# Commodore_KB_Tester.net
KiCad netlist of a schematic drawn in EAGLE
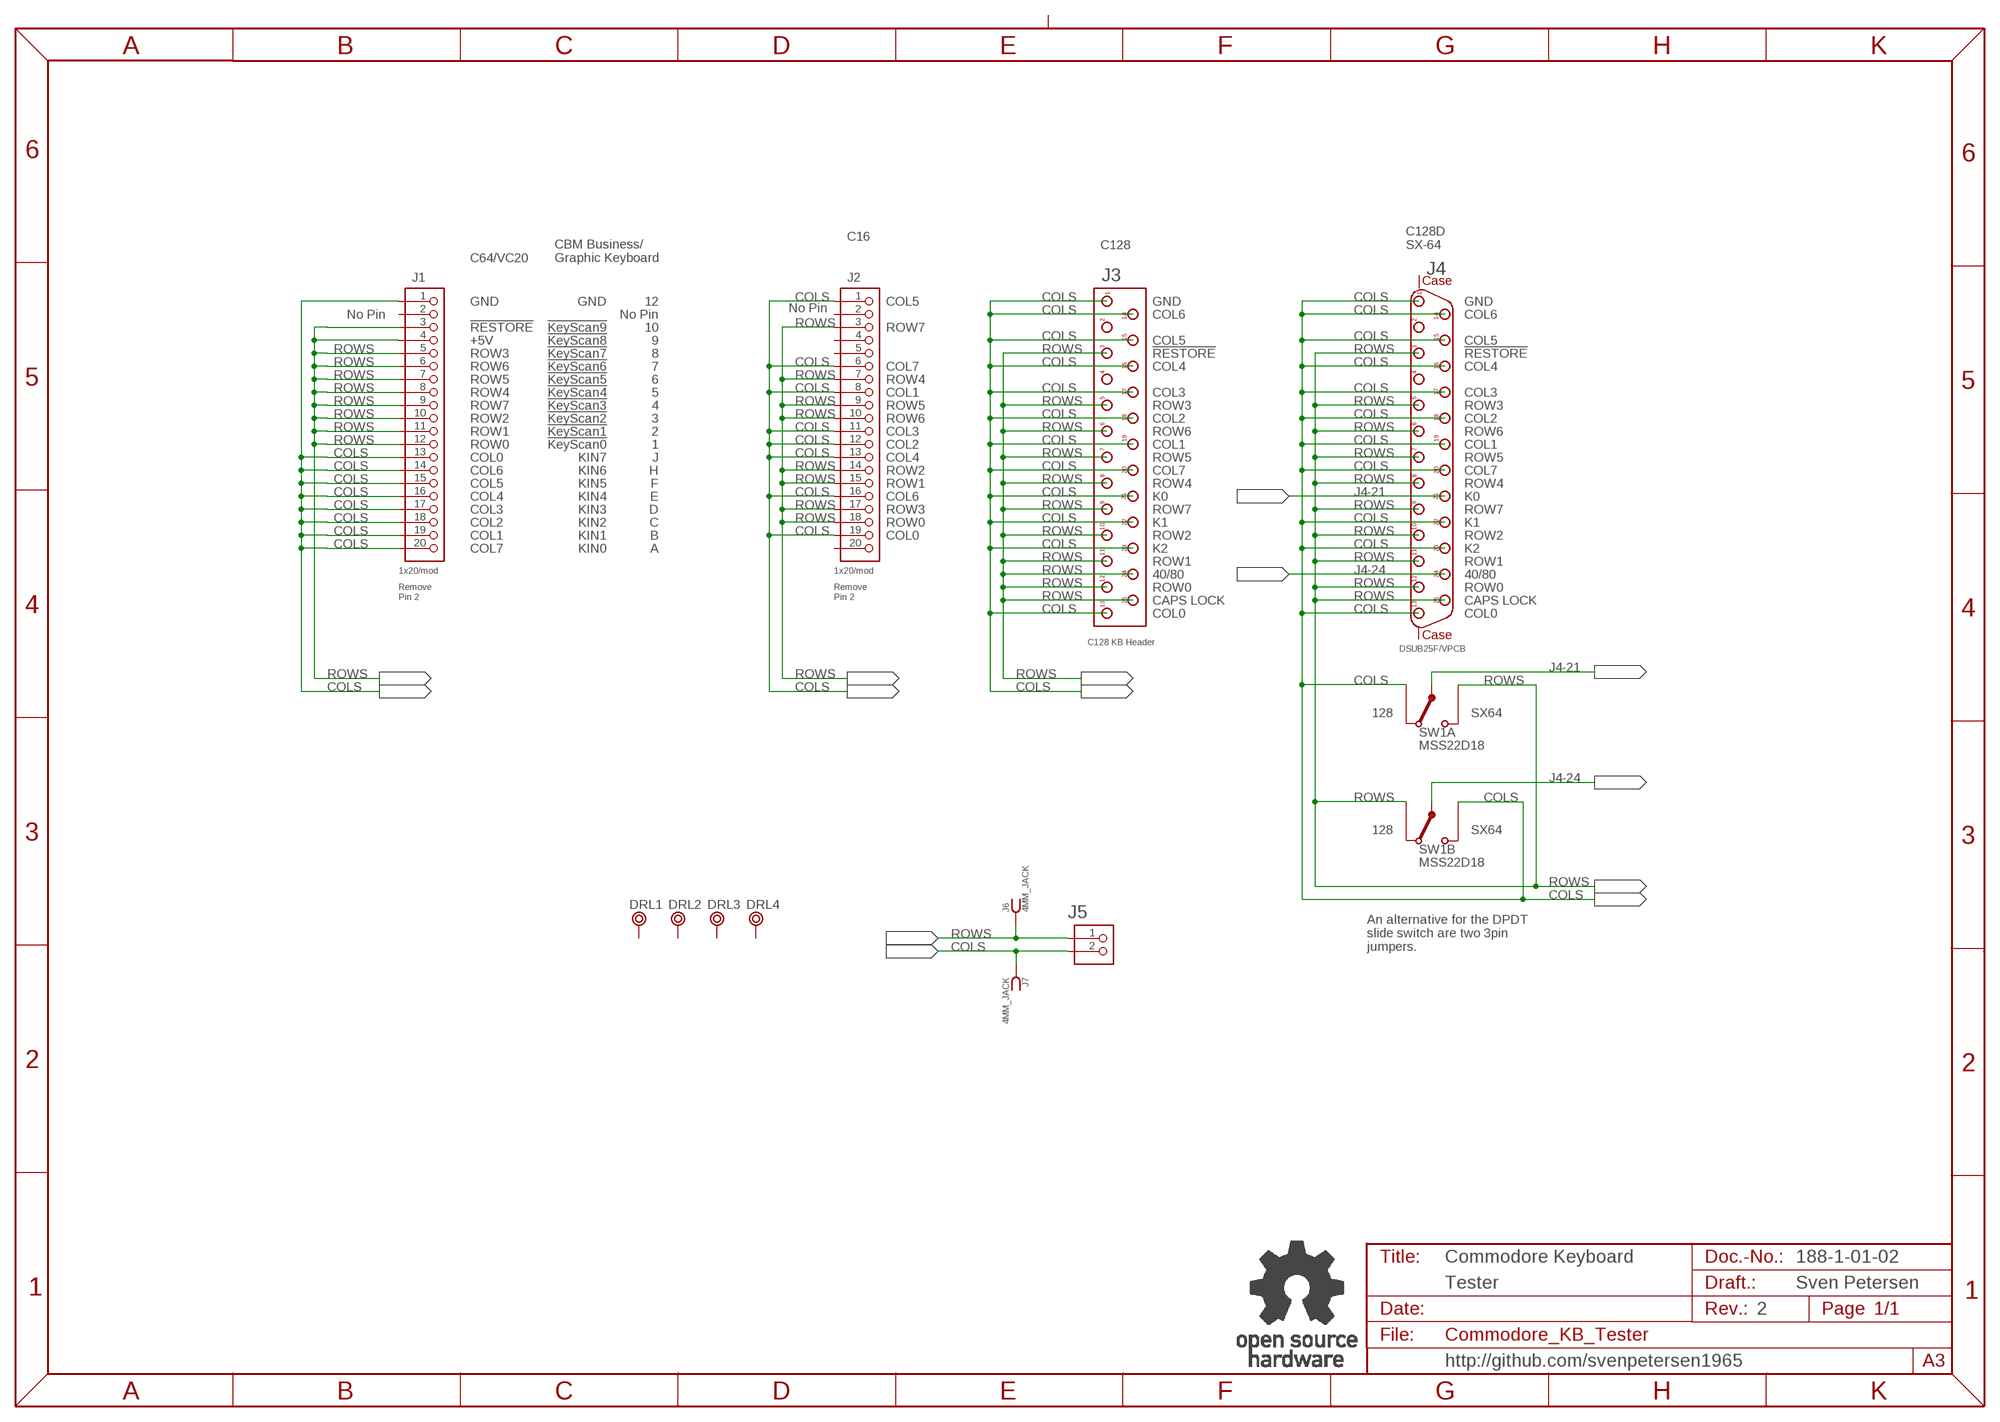
[diagram p0: schematic, sheet 1]

(export (version "E")
  (design (tool "Eeschema 10.0.6"))
  (components
    (comp (ref "DRL1")
      (value "BOHR3,5")
      (footprint "eagle-import:BOHR3,5")
      (libsource (lib "eagle-import") (part "BOHR3,5"))
    )
    (comp (ref "DRL2")
      (value "BOHR3,5")
      (footprint "eagle-import:BOHR3,5")
      (libsource (lib "eagle-import") (part "BOHR3,5"))
    )
    (comp (ref "DRL3")
      (value "BOHR3,5")
      (footprint "eagle-import:BOHR3,5")
      (libsource (lib "eagle-import") (part "BOHR3,5"))
    )
    (comp (ref "DRL4")
      (value "BOHR3,5")
      (footprint "eagle-import:BOHR3,5")
      (libsource (lib "eagle-import") (part "BOHR3,5"))
    )
    (comp (ref "J1")
      (value "1x20/mod")
      (footprint "eagle-import:1X20")
      (libsource (lib "eagle-import") (part "PINHD-1X20"))
    )
    (comp (ref "J2")
      (value "1x20/mod")
      (footprint "eagle-import:1X20")
      (libsource (lib "eagle-import") (part "PINHD-1X20"))
    )
    (comp (ref "J3")
      (value "C128 KB Header")
      (footprint "eagle-import:C128KB_HEADER")
      (libsource (lib "eagle-import") (part "C128_KBHEADER"))
    )
    (comp (ref "J4")
      (value "DSUB25F/VPCB")
      (footprint "eagle-import:DS25F-V")
      (libsource (lib "eagle-import") (part "DS25F-V-CL"))
    )
    (comp (ref "J5")
      (value "PINHD-1X2")
      (footprint "eagle-import:1X02")
      (libsource (lib "eagle-import") (part "PINHD-1X2"))
    )
    (comp (ref "J6")
      (value "4MM_JACK")
      (footprint "eagle-import:JACK4MM")
      (libsource (lib "eagle-import") (part "4MM_JACK"))
    )
    (comp (ref "J7")
      (value "4MM_JACK")
      (footprint "eagle-import:JACK4MM")
      (libsource (lib "eagle-import") (part "4MM_JACK"))
    )
    (comp (ref "SW1")
      (value "MSS22D18")
      (footprint "eagle-import:DPDT_9MM")
      (libsource (lib "eagle-import") (part "DPDT_9MM"))
    )
    (comp (ref "U$12")
      (value "OPEN_SOURCE_HW")
      (footprint "eagle-import:OPENHW")
      (libsource (lib "eagle-import") (part "OPEN_SOURCE_HW"))
    )
  )
  (nets
    (net (code "1") (name "/COLS") (class "Default")
      (node (ref "J1") (pin "1") (pinfunction "1_1") (pintype "passive"))
      (node (ref "J1") (pin "13") (pinfunction "13_13") (pintype "passive"))
      (node (ref "J1") (pin "14") (pinfunction "14_14") (pintype "passive"))
      (node (ref "J1") (pin "15") (pinfunction "15_15") (pintype "passive"))
      (node (ref "J1") (pin "16") (pinfunction "16_16") (pintype "passive"))
      (node (ref "J1") (pin "17") (pinfunction "17_17") (pintype "passive"))
      (node (ref "J1") (pin "18") (pinfunction "18_18") (pintype "passive"))
      (node (ref "J1") (pin "19") (pinfunction "19_19") (pintype "passive"))
      (node (ref "J1") (pin "20") (pinfunction "20_20") (pintype "passive"))
      (node (ref "J2") (pin "1") (pinfunction "1_1") (pintype "passive"))
      (node (ref "J2") (pin "11") (pinfunction "11_11") (pintype "passive"))
      (node (ref "J2") (pin "12") (pinfunction "12_12") (pintype "passive"))
      (node (ref "J2") (pin "13") (pinfunction "13_13") (pintype "passive"))
      (node (ref "J2") (pin "16") (pinfunction "16_16") (pintype "passive"))
      (node (ref "J2") (pin "19") (pinfunction "19_19") (pintype "passive"))
      (node (ref "J2") (pin "6") (pinfunction "6_6") (pintype "passive"))
      (node (ref "J2") (pin "8") (pinfunction "8_8") (pintype "passive"))
      (node (ref "J3") (pin "1") (pinfunction "1_1") (pintype "passive"))
      (node (ref "J3") (pin "13") (pinfunction "13_13") (pintype "passive"))
      (node (ref "J3") (pin "14") (pinfunction "14_14") (pintype "passive"))
      (node (ref "J3") (pin "15") (pinfunction "15_15") (pintype "passive"))
      (node (ref "J3") (pin "16") (pinfunction "16_16") (pintype "passive"))
      (node (ref "J3") (pin "17") (pinfunction "17_17") (pintype "passive"))
      (node (ref "J3") (pin "18") (pinfunction "18_18") (pintype "passive"))
      (node (ref "J3") (pin "19") (pinfunction "19_19") (pintype "passive"))
      (node (ref "J3") (pin "20") (pinfunction "20_20") (pintype "passive"))
      (node (ref "J3") (pin "21") (pinfunction "21_21") (pintype "passive"))
      (node (ref "J3") (pin "22") (pinfunction "22_22") (pintype "passive"))
      (node (ref "J3") (pin "23") (pinfunction "23_23") (pintype "passive"))
      (node (ref "J4") (pin "1") (pinfunction "1_1") (pintype "passive"))
      (node (ref "J4") (pin "13") (pinfunction "13_13") (pintype "passive"))
      (node (ref "J4") (pin "14") (pinfunction "14_14") (pintype "passive"))
      (node (ref "J4") (pin "15") (pinfunction "15_15") (pintype "passive"))
      (node (ref "J4") (pin "16") (pinfunction "16_16") (pintype "passive"))
      (node (ref "J4") (pin "17") (pinfunction "17_17") (pintype "passive"))
      (node (ref "J4") (pin "18") (pinfunction "18_18") (pintype "passive"))
      (node (ref "J4") (pin "19") (pinfunction "19_19") (pintype "passive"))
      (node (ref "J4") (pin "20") (pinfunction "20_20") (pintype "passive"))
      (node (ref "J4") (pin "22") (pinfunction "22_22") (pintype "passive"))
      (node (ref "J4") (pin "23") (pinfunction "23_23") (pintype "passive"))
      (node (ref "J5") (pin "2") (pinfunction "2_2") (pintype "passive"))
      (node (ref "J7") (pin "1") (pinfunction "1_1") (pintype "bidirectional"))
      (node (ref "J7") (pin "1A") (pinfunction "1_1A") (pintype "bidirectional"))
      (node (ref "SW1") (pin "3") (pinfunction "DWN_3") (pintype "bidirectional"))
      (node (ref "SW1") (pin "6") (pinfunction "UP_6") (pintype "bidirectional"))
    )
    (net (code "2") (name "/J4-21") (class "Default")
      (node (ref "J4") (pin "21") (pinfunction "21_21") (pintype "passive"))
      (node (ref "SW1") (pin "2") (pinfunction "COM_2") (pintype "bidirectional"))
    )
    (net (code "3") (name "/J4-24") (class "Default")
      (node (ref "J4") (pin "24") (pinfunction "24_24") (pintype "passive"))
      (node (ref "SW1") (pin "5") (pinfunction "COM_5") (pintype "bidirectional"))
    )
    (net (code "4") (name "/ROWS") (class "Default")
      (node (ref "J1") (pin "10") (pinfunction "10_10") (pintype "passive"))
      (node (ref "J1") (pin "11") (pinfunction "11_11") (pintype "passive"))
      (node (ref "J1") (pin "12") (pinfunction "12_12") (pintype "passive"))
      (node (ref "J1") (pin "3") (pinfunction "3_3") (pintype "passive"))
      (node (ref "J1") (pin "4") (pinfunction "4_4") (pintype "passive"))
      (node (ref "J1") (pin "5") (pinfunction "5_5") (pintype "passive"))
      (node (ref "J1") (pin "6") (pinfunction "6_6") (pintype "passive"))
      (node (ref "J1") (pin "7") (pinfunction "7_7") (pintype "passive"))
      (node (ref "J1") (pin "8") (pinfunction "8_8") (pintype "passive"))
      (node (ref "J1") (pin "9") (pinfunction "9_9") (pintype "passive"))
      (node (ref "J2") (pin "10") (pinfunction "10_10") (pintype "passive"))
      (node (ref "J2") (pin "14") (pinfunction "14_14") (pintype "passive"))
      (node (ref "J2") (pin "15") (pinfunction "15_15") (pintype "passive"))
      (node (ref "J2") (pin "17") (pinfunction "17_17") (pintype "passive"))
      (node (ref "J2") (pin "18") (pinfunction "18_18") (pintype "passive"))
      (node (ref "J2") (pin "3") (pinfunction "3_3") (pintype "passive"))
      (node (ref "J2") (pin "7") (pinfunction "7_7") (pintype "passive"))
      (node (ref "J2") (pin "9") (pinfunction "9_9") (pintype "passive"))
      (node (ref "J3") (pin "10") (pinfunction "10_10") (pintype "passive"))
      (node (ref "J3") (pin "11") (pinfunction "11_11") (pintype "passive"))
      (node (ref "J3") (pin "12") (pinfunction "12_12") (pintype "passive"))
      (node (ref "J3") (pin "24") (pinfunction "24_24") (pintype "passive"))
      (node (ref "J3") (pin "25") (pinfunction "25_25") (pintype "passive"))
      (node (ref "J3") (pin "3") (pinfunction "3_3") (pintype "passive"))
      (node (ref "J3") (pin "5") (pinfunction "5_5") (pintype "passive"))
      (node (ref "J3") (pin "6") (pinfunction "6_6") (pintype "passive"))
      (node (ref "J3") (pin "7") (pinfunction "7_7") (pintype "passive"))
      (node (ref "J3") (pin "8") (pinfunction "8_8") (pintype "passive"))
      (node (ref "J3") (pin "9") (pinfunction "9_9") (pintype "passive"))
      (node (ref "J4") (pin "10") (pinfunction "10_10") (pintype "passive"))
      (node (ref "J4") (pin "11") (pinfunction "11_11") (pintype "passive"))
      (node (ref "J4") (pin "12") (pinfunction "12_12") (pintype "passive"))
      (node (ref "J4") (pin "25") (pinfunction "25_25") (pintype "passive"))
      (node (ref "J4") (pin "3") (pinfunction "3_3") (pintype "passive"))
      (node (ref "J4") (pin "5") (pinfunction "5_5") (pintype "passive"))
      (node (ref "J4") (pin "6") (pinfunction "6_6") (pintype "passive"))
      (node (ref "J4") (pin "7") (pinfunction "7_7") (pintype "passive"))
      (node (ref "J4") (pin "8") (pinfunction "8_8") (pintype "passive"))
      (node (ref "J4") (pin "9") (pinfunction "9_9") (pintype "passive"))
      (node (ref "J5") (pin "1") (pinfunction "1_1") (pintype "passive"))
      (node (ref "J6") (pin "1") (pinfunction "1_1") (pintype "bidirectional"))
      (node (ref "J6") (pin "1A") (pinfunction "1_1A") (pintype "bidirectional"))
      (node (ref "SW1") (pin "1") (pinfunction "UP_1") (pintype "bidirectional"))
      (node (ref "SW1") (pin "4") (pinfunction "DWN_4") (pintype "bidirectional"))
    )
    (net (code "5") (name "unconnected-(DRL1-PadP$1)") (class "Default")
      (node (ref "DRL1") (pin "P$1") (pinfunction "P$1_P$1") (pintype "passive"))
    )
    (net (code "6") (name "unconnected-(DRL2-PadP$1)") (class "Default")
      (node (ref "DRL2") (pin "P$1") (pinfunction "P$1_P$1") (pintype "passive"))
    )
    (net (code "7") (name "unconnected-(DRL3-PadP$1)") (class "Default")
      (node (ref "DRL3") (pin "P$1") (pinfunction "P$1_P$1") (pintype "passive"))
    )
    (net (code "8") (name "unconnected-(DRL4-PadP$1)") (class "Default")
      (node (ref "DRL4") (pin "P$1") (pinfunction "P$1_P$1") (pintype "passive"))
    )
    (net (code "9") (name "unconnected-(J1-Pad2)") (class "Default")
      (node (ref "J1") (pin "2") (pinfunction "2_2") (pintype "passive"))
    )
    (net (code "10") (name "unconnected-(J2-Pad2)") (class "Default")
      (node (ref "J2") (pin "2") (pinfunction "2_2") (pintype "passive"))
    )
    (net (code "11") (name "unconnected-(J2-Pad4)") (class "Default")
      (node (ref "J2") (pin "4") (pinfunction "4_4") (pintype "passive"))
    )
    (net (code "12") (name "unconnected-(J2-Pad5)") (class "Default")
      (node (ref "J2") (pin "5") (pinfunction "5_5") (pintype "passive"))
    )
    (net (code "13") (name "unconnected-(J2-Pad20)") (class "Default")
      (node (ref "J2") (pin "20") (pinfunction "20_20") (pintype "passive"))
    )
    (net (code "14") (name "unconnected-(J3-Pad2)") (class "Default")
      (node (ref "J3") (pin "2") (pinfunction "2_2") (pintype "passive"))
    )
    (net (code "15") (name "unconnected-(J3-Pad4)") (class "Default")
      (node (ref "J3") (pin "4") (pinfunction "4_4") (pintype "passive"))
    )
    (net (code "16") (name "unconnected-(J4-CL1-PadPE1)") (class "Default")
      (node (ref "J4") (pin "PE1") (pinfunction "CL1_PE1") (pintype "bidirectional"))
    )
    (net (code "17") (name "unconnected-(J4-CL2-PadPE2)") (class "Default")
      (node (ref "J4") (pin "PE2") (pinfunction "CL2_PE2") (pintype "bidirectional"))
    )
    (net (code "18") (name "unconnected-(J4-Pad2)") (class "Default")
      (node (ref "J4") (pin "2") (pinfunction "2_2") (pintype "passive"))
    )
    (net (code "19") (name "unconnected-(J4-Pad4)") (class "Default")
      (node (ref "J4") (pin "4") (pinfunction "4_4") (pintype "passive"))
    )
  )
)
